# 03_ANALOG.net
KiCad netlist of a schematic drawn in Altium Designer
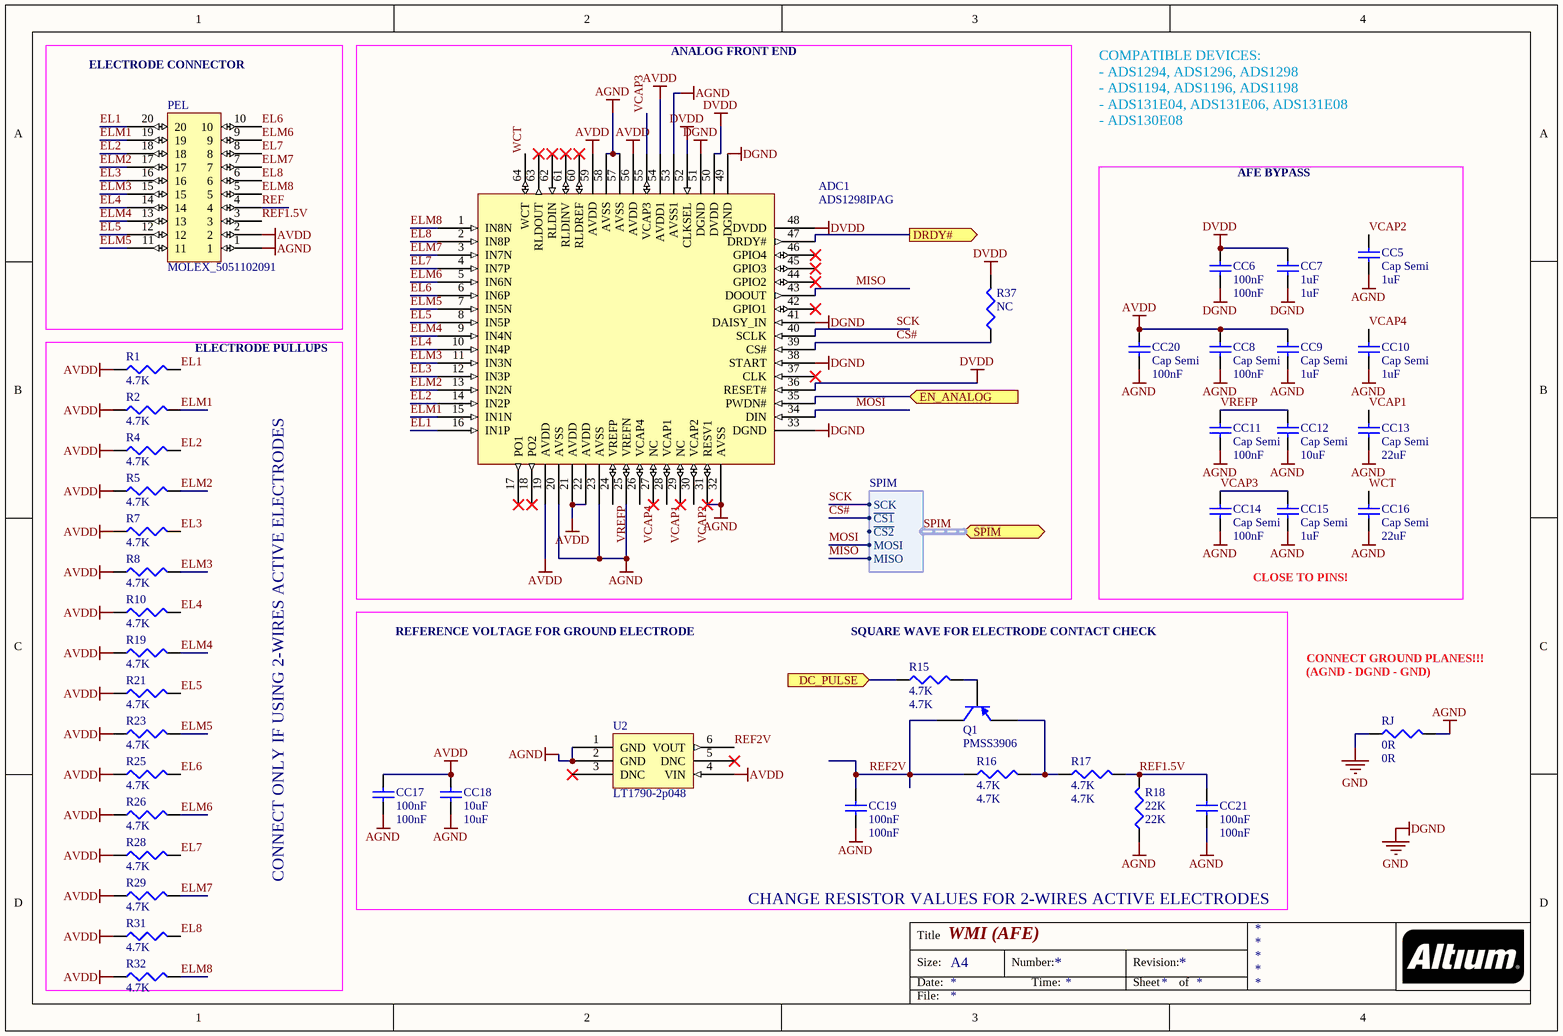
[diagram p0: 03_ANALOG.SchDoc]

(export (version "E")
  (design (tool "Eeschema 10.0.6"))
  (components
    (comp (ref "ADC1")
      (value "ADS1298IPAG")
      (footprint "Atmel Microcontroller 32-Bit ARM:LQFP64_M")
      (libsource (lib "Schlib1") (part "ADS1298"))
    )
    (comp (ref "CC5")
      (value "Cap Semi")
      (footprint "0402")
      (description "Capacitor (Semiconductor SIM Model)")
      (fields (field (name "ALTIUM_VALUE") "1uF") (field (name "PUBLISHER") "Altium Limited"))
      (libsource (lib "Miscellaneous Devices") (part "Cap Semi"))
    )
    (comp (ref "CC6")
      (value "100nF")
      (footprint "0402")
      (description "Capacitor (Semiconductor SIM Model)")
      (fields (field (name "ALTIUM_VALUE") "100nF") (field (name "PUBLISHER") "Altium Limited"))
      (libsource (lib "Miscellaneous Devices") (part "Cap Semi"))
    )
    (comp (ref "CC7")
      (value "1uF")
      (footprint "0402")
      (description "Capacitor (Semiconductor SIM Model)")
      (fields (field (name "ALTIUM_VALUE") "1uF") (field (name "PUBLISHER") "Altium Limited"))
      (libsource (lib "Miscellaneous Devices") (part "Cap Semi"))
    )
    (comp (ref "CC8")
      (value "Cap Semi")
      (footprint "0402")
      (description "Capacitor (Semiconductor SIM Model)")
      (fields (field (name "ALTIUM_VALUE") "100nF") (field (name "PUBLISHER") "Altium Limited"))
      (libsource (lib "Miscellaneous Devices") (part "Cap Semi"))
    )
    (comp (ref "CC9")
      (value "Cap Semi")
      (footprint "0402")
      (description "Capacitor (Semiconductor SIM Model)")
      (fields (field (name "ALTIUM_VALUE") "1uF") (field (name "PUBLISHER") "Altium Limited"))
      (libsource (lib "Miscellaneous Devices") (part "Cap Semi"))
    )
    (comp (ref "CC10")
      (value "Cap Semi")
      (footprint "0402")
      (description "Capacitor (Semiconductor SIM Model)")
      (fields (field (name "ALTIUM_VALUE") "1uF") (field (name "PUBLISHER") "Altium Limited"))
      (libsource (lib "Miscellaneous Devices") (part "Cap Semi"))
    )
    (comp (ref "CC11")
      (value "Cap Semi")
      (footprint "0402")
      (description "Capacitor (Semiconductor SIM Model)")
      (fields (field (name "ALTIUM_VALUE") "100nF") (field (name "PUBLISHER") "Altium Limited"))
      (libsource (lib "Miscellaneous Devices") (part "Cap Semi"))
    )
    (comp (ref "CC12")
      (value "Cap Semi")
      (footprint "0402")
      (description "Capacitor (Semiconductor SIM Model)")
      (fields (field (name "ALTIUM_VALUE") "10uF") (field (name "PUBLISHER") "Altium Limited"))
      (libsource (lib "Miscellaneous Devices") (part "Cap Semi"))
    )
    (comp (ref "CC13")
      (value "Cap Semi")
      (footprint "J1-0603")
      (description "Capacitor (Semiconductor SIM Model)")
      (fields (field (name "ALTIUM_VALUE") "22uF") (field (name "PUBLISHER") "Altium Limited"))
      (libsource (lib "Miscellaneous Devices") (part "Cap Semi"))
    )
    (comp (ref "CC14")
      (value "Cap Semi")
      (footprint "0402")
      (description "Capacitor (Semiconductor SIM Model)")
      (fields (field (name "ALTIUM_VALUE") "100nF") (field (name "PUBLISHER") "Altium Limited"))
      (libsource (lib "Miscellaneous Devices") (part "Cap Semi"))
    )
    (comp (ref "CC15")
      (value "Cap Semi")
      (footprint "0402")
      (description "Capacitor (Semiconductor SIM Model)")
      (fields (field (name "ALTIUM_VALUE") "1uF") (field (name "PUBLISHER") "Altium Limited"))
      (libsource (lib "Miscellaneous Devices") (part "Cap Semi"))
    )
    (comp (ref "CC16")
      (value "Cap Semi")
      (footprint "1608[0603]")
      (description "Capacitor (Semiconductor SIM Model)")
      (fields (field (name "ALTIUM_VALUE") "22uF") (field (name "PUBLISHER") "Altium Limited"))
      (libsource (lib "Miscellaneous Devices") (part "Cap Semi"))
    )
    (comp (ref "CC17")
      (value "100nF")
      (footprint "0402")
      (description "Capacitor (Semiconductor SIM Model)")
      (fields (field (name "ALTIUM_VALUE") "100nF") (field (name "PUBLISHER") "Altium Limited"))
      (libsource (lib "Miscellaneous Devices") (part "Cap Semi"))
    )
    (comp (ref "CC18")
      (value "10uF")
      (footprint "0402")
      (description "Capacitor (Semiconductor SIM Model)")
      (fields (field (name "ALTIUM_VALUE") "10uF") (field (name "PUBLISHER") "Altium Limited"))
      (libsource (lib "Miscellaneous Devices") (part "Cap Semi"))
    )
    (comp (ref "CC19")
      (value "100nF")
      (footprint "0402")
      (description "Capacitor (Semiconductor SIM Model)")
      (fields (field (name "ALTIUM_VALUE") "100nF") (field (name "PUBLISHER") "Altium Limited"))
      (libsource (lib "Miscellaneous Devices") (part "Cap Semi"))
    )
    (comp (ref "CC20")
      (value "Cap Semi")
      (footprint "0402")
      (description "Capacitor (Semiconductor SIM Model)")
      (fields (field (name "ALTIUM_VALUE") "100nF") (field (name "PUBLISHER") "Altium Limited"))
      (libsource (lib "Miscellaneous Devices") (part "Cap Semi"))
    )
    (comp (ref "CC21")
      (value "100nF")
      (footprint "0402")
      (description "Capacitor (Semiconductor SIM Model)")
      (fields (field (name "ALTIUM_VALUE") "100nF") (field (name "PUBLISHER") "Altium Limited"))
      (libsource (lib "Miscellaneous Devices") (part "Cap Semi"))
    )
    (comp (ref "PEL")
      (value "MOLEX_5051102091")
      (footprint "MOLEX_5051102091")
      (libsource (lib "Schlib1") (part "MOLEX_5051102091"))
    )
    (comp (ref "Q1")
      (value "PMSS3906")
      (footprint "SOT323_N")
      (description "PNP Switching Transistor")
      (fields (field (name "PUBLISHER") "Altium Limited"))
      (libsource (lib "Philips Discrete BJT - Low Power") (part "PMSS3906"))
    )
    (comp (ref "R1")
      (value "4.7K")
      (footprint "0402")
      (description "Resistor")
      (fields (field (name "PUBLISHER") "Altium Limited"))
      (libsource (lib "Miscellaneous Devices") (part "Res3"))
    )
    (comp (ref "R2")
      (value "4.7K")
      (footprint "0402")
      (description "Resistor")
      (fields (field (name "PUBLISHER") "Altium Limited"))
      (libsource (lib "Miscellaneous Devices") (part "Res3"))
    )
    (comp (ref "R4")
      (value "4.7K")
      (footprint "0402")
      (description "Resistor")
      (fields (field (name "PUBLISHER") "Altium Limited"))
      (libsource (lib "Miscellaneous Devices") (part "Res3"))
    )
    (comp (ref "R5")
      (value "4.7K")
      (footprint "0402")
      (description "Resistor")
      (fields (field (name "PUBLISHER") "Altium Limited"))
      (libsource (lib "Miscellaneous Devices") (part "Res3"))
    )
    (comp (ref "R7")
      (value "4.7K")
      (footprint "0402")
      (description "Resistor")
      (fields (field (name "PUBLISHER") "Altium Limited"))
      (libsource (lib "Miscellaneous Devices") (part "Res3"))
    )
    (comp (ref "R8")
      (value "4.7K")
      (footprint "0402")
      (description "Resistor")
      (fields (field (name "PUBLISHER") "Altium Limited"))
      (libsource (lib "Miscellaneous Devices") (part "Res3"))
    )
    (comp (ref "R10")
      (value "4.7K")
      (footprint "0402")
      (description "Resistor")
      (fields (field (name "PUBLISHER") "Altium Limited"))
      (libsource (lib "Miscellaneous Devices") (part "Res3"))
    )
    (comp (ref "R15")
      (value "4.7K")
      (footprint "0402")
      (description "Resistor")
      (fields (field (name "ALTIUM_VALUE") "4.7K") (field (name "PUBLISHER") "Altium Limited"))
      (libsource (lib "Miscellaneous Devices") (part "Res3"))
    )
    (comp (ref "R16")
      (value "4.7K")
      (footprint "0402")
      (description "Resistor")
      (fields (field (name "ALTIUM_VALUE") "4.7K") (field (name "PUBLISHER") "Altium Limited"))
      (libsource (lib "Miscellaneous Devices") (part "Res3"))
    )
    (comp (ref "R17")
      (value "4.7K")
      (footprint "0402")
      (description "Resistor")
      (fields (field (name "ALTIUM_VALUE") "4.7K") (field (name "PUBLISHER") "Altium Limited"))
      (libsource (lib "Miscellaneous Devices") (part "Res3"))
    )
    (comp (ref "R18")
      (value "22K")
      (footprint "0402")
      (description "Resistor")
      (fields (field (name "ALTIUM_VALUE") "22K") (field (name "PUBLISHER") "Altium Limited"))
      (libsource (lib "Miscellaneous Devices") (part "Res3"))
    )
    (comp (ref "R19")
      (value "4.7K")
      (footprint "0402")
      (description "Resistor")
      (fields (field (name "PUBLISHER") "Altium Limited"))
      (libsource (lib "Miscellaneous Devices") (part "Res3"))
    )
    (comp (ref "R21")
      (value "4.7K")
      (footprint "0402")
      (description "Resistor")
      (fields (field (name "PUBLISHER") "Altium Limited"))
      (libsource (lib "Miscellaneous Devices") (part "Res3"))
    )
    (comp (ref "R23")
      (value "4.7K")
      (footprint "0402")
      (description "Resistor")
      (fields (field (name "PUBLISHER") "Altium Limited"))
      (libsource (lib "Miscellaneous Devices") (part "Res3"))
    )
    (comp (ref "R25")
      (value "4.7K")
      (footprint "0402")
      (description "Resistor")
      (fields (field (name "PUBLISHER") "Altium Limited"))
      (libsource (lib "Miscellaneous Devices") (part "Res3"))
    )
    (comp (ref "R26")
      (value "4.7K")
      (footprint "0402")
      (description "Resistor")
      (fields (field (name "PUBLISHER") "Altium Limited"))
      (libsource (lib "Miscellaneous Devices") (part "Res3"))
    )
    (comp (ref "R28")
      (value "4.7K")
      (footprint "0402")
      (description "Resistor")
      (fields (field (name "PUBLISHER") "Altium Limited"))
      (libsource (lib "Miscellaneous Devices") (part "Res3"))
    )
    (comp (ref "R29")
      (value "4.7K")
      (footprint "0402")
      (description "Resistor")
      (fields (field (name "PUBLISHER") "Altium Limited"))
      (libsource (lib "Miscellaneous Devices") (part "Res3"))
    )
    (comp (ref "R31")
      (value "4.7K")
      (footprint "0402")
      (description "Resistor")
      (fields (field (name "PUBLISHER") "Altium Limited"))
      (libsource (lib "Miscellaneous Devices") (part "Res3"))
    )
    (comp (ref "R32")
      (value "4.7K")
      (footprint "0402")
      (description "Resistor")
      (fields (field (name "PUBLISHER") "Altium Limited"))
      (libsource (lib "Miscellaneous Devices") (part "Res3"))
    )
    (comp (ref "R37")
      (value "NC")
      (footprint "0402")
      (description "Resistor")
      (fields (field (name "PUBLISHER") "Altium Limited"))
      (libsource (lib "Miscellaneous Devices") (part "Res3"))
    )
    (comp (ref "RJ")
      (value "0R")
      (footprint "0402")
      (description "Resistor")
      (fields (field (name "ALTIUM_VALUE") "0R") (field (name "PUBLISHER") "Altium Limited"))
      (libsource (lib "Miscellaneous Devices") (part "Res3"))
    )
    (comp (ref "U2")
      (value "LT1790-2p048")
      (footprint "SOT-23_A_N")
      (libsource (lib "Schlib1") (part "LT1790"))
    )
  )
  (nets
    (net (code "2") (name "/CS#") (class "Default")
      (node (ref "ADC1") (pin "39") (pinfunction "CS#_39") (pintype "input"))
      (node (ref "R37") (pin "1") (pinfunction "1_1") (pintype "passive"))
    )
    (net (code "3") (name "/DC_PULSE") (class "Default")
      (node (ref "R15") (pin "1") (pinfunction "1_1") (pintype "passive"))
    )
    (net (code "4") (name "/DRDY#") (class "Default")
      (node (ref "ADC1") (pin "47") (pinfunction "DRDY#_47") (pintype "output"))
    )
    (net (code "5") (name "/EL1") (class "Default")
      (node (ref "ADC1") (pin "16") (pinfunction "IN1P_16") (pintype "input"))
      (node (ref "PEL") (pin "20") (pinfunction "20_20") (pintype "bidirectional"))
      (node (ref "R1") (pin "2") (pinfunction "2_2") (pintype "passive"))
    )
    (net (code "6") (name "/EL2") (class "Default")
      (node (ref "ADC1") (pin "14") (pinfunction "IN2P_14") (pintype "input"))
      (node (ref "PEL") (pin "18") (pinfunction "18_18") (pintype "bidirectional"))
      (node (ref "R4") (pin "2") (pinfunction "2_2") (pintype "passive"))
    )
    (net (code "7") (name "/EL3") (class "Default")
      (node (ref "ADC1") (pin "12") (pinfunction "IN3P_12") (pintype "input"))
      (node (ref "PEL") (pin "16") (pinfunction "16_16") (pintype "bidirectional"))
      (node (ref "R7") (pin "2") (pinfunction "2_2") (pintype "passive"))
    )
    (net (code "8") (name "/EL4") (class "Default")
      (node (ref "ADC1") (pin "10") (pinfunction "IN4P_10") (pintype "input"))
      (node (ref "PEL") (pin "14") (pinfunction "14_14") (pintype "bidirectional"))
      (node (ref "R10") (pin "2") (pinfunction "2_2") (pintype "passive"))
    )
    (net (code "9") (name "/EL5") (class "Default")
      (node (ref "ADC1") (pin "8") (pinfunction "IN5P_8") (pintype "input"))
      (node (ref "PEL") (pin "12") (pinfunction "12_12") (pintype "bidirectional"))
      (node (ref "R21") (pin "2") (pinfunction "2_2") (pintype "passive"))
    )
    (net (code "10") (name "/EL6") (class "Default")
      (node (ref "ADC1") (pin "6") (pinfunction "IN6P_6") (pintype "input"))
      (node (ref "PEL") (pin "10") (pinfunction "10_10") (pintype "bidirectional"))
      (node (ref "R25") (pin "2") (pinfunction "2_2") (pintype "passive"))
    )
    (net (code "11") (name "/EL7") (class "Default")
      (node (ref "ADC1") (pin "4") (pinfunction "IN7P_4") (pintype "input"))
      (node (ref "PEL") (pin "8") (pinfunction "8_8") (pintype "bidirectional"))
      (node (ref "R28") (pin "2") (pinfunction "2_2") (pintype "passive"))
    )
    (net (code "12") (name "/EL8") (class "Default")
      (node (ref "ADC1") (pin "2") (pinfunction "IN8P_2") (pintype "input"))
      (node (ref "PEL") (pin "6") (pinfunction "6_6") (pintype "bidirectional"))
      (node (ref "R31") (pin "2") (pinfunction "2_2") (pintype "passive"))
    )
    (net (code "13") (name "/ELM1") (class "Default")
      (node (ref "ADC1") (pin "15") (pinfunction "IN1N_15") (pintype "input"))
      (node (ref "PEL") (pin "19") (pinfunction "19_19") (pintype "bidirectional"))
      (node (ref "R2") (pin "2") (pinfunction "2_2") (pintype "passive"))
    )
    (net (code "14") (name "/ELM2") (class "Default")
      (node (ref "ADC1") (pin "13") (pinfunction "IN2N_13") (pintype "input"))
      (node (ref "PEL") (pin "17") (pinfunction "17_17") (pintype "bidirectional"))
      (node (ref "R5") (pin "2") (pinfunction "2_2") (pintype "passive"))
    )
    (net (code "15") (name "/ELM3") (class "Default")
      (node (ref "ADC1") (pin "11") (pinfunction "IN3N_11") (pintype "input"))
      (node (ref "PEL") (pin "15") (pinfunction "15_15") (pintype "bidirectional"))
      (node (ref "R8") (pin "2") (pinfunction "2_2") (pintype "passive"))
    )
    (net (code "16") (name "/ELM4") (class "Default")
      (node (ref "ADC1") (pin "9") (pinfunction "IN4N_9") (pintype "input"))
      (node (ref "PEL") (pin "13") (pinfunction "13_13") (pintype "bidirectional"))
      (node (ref "R19") (pin "2") (pinfunction "2_2") (pintype "passive"))
    )
    (net (code "17") (name "/ELM5") (class "Default")
      (node (ref "ADC1") (pin "7") (pinfunction "IN5N_7") (pintype "input"))
      (node (ref "PEL") (pin "11") (pinfunction "11_11") (pintype "bidirectional"))
      (node (ref "R23") (pin "2") (pinfunction "2_2") (pintype "passive"))
    )
    (net (code "18") (name "/ELM6") (class "Default")
      (node (ref "ADC1") (pin "5") (pinfunction "IN6N_5") (pintype "input"))
      (node (ref "PEL") (pin "9") (pinfunction "9_9") (pintype "bidirectional"))
      (node (ref "R26") (pin "2") (pinfunction "2_2") (pintype "passive"))
    )
    (net (code "19") (name "/ELM7") (class "Default")
      (node (ref "ADC1") (pin "3") (pinfunction "IN7N_3") (pintype "input"))
      (node (ref "PEL") (pin "7") (pinfunction "7_7") (pintype "bidirectional"))
      (node (ref "R29") (pin "2") (pinfunction "2_2") (pintype "passive"))
    )
    (net (code "20") (name "/ELM8") (class "Default")
      (node (ref "ADC1") (pin "1") (pinfunction "IN8N_1") (pintype "input"))
      (node (ref "PEL") (pin "5") (pinfunction "5_5") (pintype "bidirectional"))
      (node (ref "R32") (pin "2") (pinfunction "2_2") (pintype "passive"))
    )
    (net (code "21") (name "/EN_ANALOG") (class "Default")
      (node (ref "ADC1") (pin "35") (pinfunction "PWDN#_35") (pintype "input"))
    )
    (net (code "22") (name "/MISO") (class "Default")
      (node (ref "ADC1") (pin "43") (pinfunction "DOOUT_43") (pintype "output"))
    )
    (net (code "23") (name "/MOSI") (class "Default")
      (node (ref "ADC1") (pin "34") (pinfunction "DIN_34") (pintype "input"))
    )
    (net (code "24") (name "/REF") (class "Default")
      (node (ref "PEL") (pin "4") (pinfunction "4_4") (pintype "bidirectional"))
    )
    (net (code "25") (name "/REF1.5V") (class "Default")
      (node (ref "CC21") (pin "2") (pinfunction "2_2") (pintype "passive"))
      (node (ref "PEL") (pin "3") (pinfunction "3_3") (pintype "bidirectional"))
      (node (ref "R17") (pin "2") (pinfunction "2_2") (pintype "passive"))
      (node (ref "R18") (pin "2") (pinfunction "2_2") (pintype "passive"))
    )
    (net (code "26") (name "/REF2V") (class "Default")
      (node (ref "CC19") (pin "2") (pinfunction "2_2") (pintype "passive"))
      (node (ref "Q1") (pin "3") (pinfunction "C_3") (pintype "passive"))
      (node (ref "R16") (pin "1") (pinfunction "1_1") (pintype "passive"))
      (node (ref "U2") (pin "6") (pinfunction "VOUT_6") (pintype "output"))
    )
    (net (code "27") (name "/SCK") (class "Default")
      (node (ref "ADC1") (pin "40") (pinfunction "SCLK_40") (pintype "input"))
    )
    (net (code "29") (name "/VCAP1") (class "Default")
      (node (ref "ADC1") (pin "28") (pinfunction "VCAP1_28") (pintype "bidirectional"))
      (node (ref "CC13") (pin "2") (pinfunction "2_2") (pintype "passive"))
    )
    (net (code "30") (name "/VCAP2") (class "Default")
      (node (ref "ADC1") (pin "30") (pinfunction "VCAP2_30") (pintype "bidirectional"))
      (node (ref "CC5") (pin "2") (pinfunction "2_2") (pintype "passive"))
    )
    (net (code "31") (name "/VCAP3") (class "Default")
      (node (ref "ADC1") (pin "55") (pinfunction "VCAP3_55") (pintype "bidirectional"))
      (node (ref "CC14") (pin "2") (pinfunction "2_2") (pintype "passive"))
      (node (ref "CC15") (pin "2") (pinfunction "2_2") (pintype "passive"))
    )
    (net (code "32") (name "/VCAP4") (class "Default")
      (node (ref "ADC1") (pin "26") (pinfunction "VCAP4_26") (pintype "bidirectional"))
      (node (ref "CC10") (pin "2") (pinfunction "2_2") (pintype "passive"))
    )
    (net (code "33") (name "/VREFP") (class "Default")
      (node (ref "ADC1") (pin "24") (pinfunction "VREFP_24") (pintype "bidirectional"))
      (node (ref "CC11") (pin "2") (pinfunction "2_2") (pintype "passive"))
      (node (ref "CC12") (pin "2") (pinfunction "2_2") (pintype "passive"))
    )
    (net (code "34") (name "/WCT") (class "Default")
      (node (ref "ADC1") (pin "64") (pinfunction "WCT_64") (pintype "bidirectional"))
      (node (ref "CC16") (pin "2") (pinfunction "2_2") (pintype "passive"))
    )
    (net (code "35") (name "AGND") (class "Default")
      (node (ref "ADC1") (pin "20") (pinfunction "AVSS_20") (pintype "power_in"))
      (node (ref "ADC1") (pin "23") (pinfunction "AVSS_23") (pintype "power_in"))
      (node (ref "ADC1") (pin "25") (pinfunction "VREFN_25") (pintype "bidirectional"))
      (node (ref "ADC1") (pin "31") (pinfunction "RESV1_31") (pintype "bidirectional"))
      (node (ref "ADC1") (pin "32") (pinfunction "AVSS_32") (pintype "power_in"))
      (node (ref "ADC1") (pin "53") (pinfunction "AVSS1_53") (pintype "power_in"))
      (node (ref "ADC1") (pin "57") (pinfunction "AVSS_57") (pintype "power_in"))
      (node (ref "ADC1") (pin "58") (pinfunction "AVSS_58") (pintype "power_in"))
      (node (ref "CC10") (pin "1") (pinfunction "1_1") (pintype "passive"))
      (node (ref "CC11") (pin "1") (pinfunction "1_1") (pintype "passive"))
      (node (ref "CC12") (pin "1") (pinfunction "1_1") (pintype "passive"))
      (node (ref "CC13") (pin "1") (pinfunction "1_1") (pintype "passive"))
      (node (ref "CC14") (pin "1") (pinfunction "1_1") (pintype "passive"))
      (node (ref "CC15") (pin "1") (pinfunction "1_1") (pintype "passive"))
      (node (ref "CC16") (pin "1") (pinfunction "1_1") (pintype "passive"))
      (node (ref "CC17") (pin "1") (pinfunction "1_1") (pintype "passive"))
      (node (ref "CC18") (pin "1") (pinfunction "1_1") (pintype "passive"))
      (node (ref "CC19") (pin "1") (pinfunction "1_1") (pintype "passive"))
      (node (ref "CC20") (pin "1") (pinfunction "1_1") (pintype "passive"))
      (node (ref "CC21") (pin "1") (pinfunction "1_1") (pintype "passive"))
      (node (ref "CC5") (pin "1") (pinfunction "1_1") (pintype "passive"))
      (node (ref "CC8") (pin "1") (pinfunction "1_1") (pintype "passive"))
      (node (ref "CC9") (pin "1") (pinfunction "1_1") (pintype "passive"))
      (node (ref "PEL") (pin "1") (pinfunction "1_1") (pintype "bidirectional"))
      (node (ref "R18") (pin "1") (pinfunction "1_1") (pintype "passive"))
      (node (ref "RJ") (pin "2") (pinfunction "2_2") (pintype "passive"))
      (node (ref "U2") (pin "1") (pinfunction "GND_1") (pintype "power_in"))
      (node (ref "U2") (pin "2") (pinfunction "GND_2") (pintype "power_in"))
    )
    (net (code "36") (name "AVDD") (class "Default")
      (node (ref "ADC1") (pin "19") (pinfunction "AVDD_19") (pintype "power_in"))
      (node (ref "ADC1") (pin "21") (pinfunction "AVDD_21") (pintype "power_in"))
      (node (ref "ADC1") (pin "22") (pinfunction "AVDD_22") (pintype "power_in"))
      (node (ref "ADC1") (pin "54") (pinfunction "AVDD1_54") (pintype "power_in"))
      (node (ref "ADC1") (pin "56") (pinfunction "AVDD_56") (pintype "power_in"))
      (node (ref "ADC1") (pin "59") (pinfunction "AVDD_59") (pintype "power_in"))
      (node (ref "CC17") (pin "2") (pinfunction "2_2") (pintype "passive"))
      (node (ref "CC18") (pin "2") (pinfunction "2_2") (pintype "passive"))
      (node (ref "CC20") (pin "2") (pinfunction "2_2") (pintype "passive"))
      (node (ref "CC8") (pin "2") (pinfunction "2_2") (pintype "passive"))
      (node (ref "CC9") (pin "2") (pinfunction "2_2") (pintype "passive"))
      (node (ref "PEL") (pin "2") (pinfunction "2_2") (pintype "bidirectional"))
      (node (ref "R1") (pin "1") (pinfunction "1_1") (pintype "passive"))
      (node (ref "R10") (pin "1") (pinfunction "1_1") (pintype "passive"))
      (node (ref "R19") (pin "1") (pinfunction "1_1") (pintype "passive"))
      (node (ref "R2") (pin "1") (pinfunction "1_1") (pintype "passive"))
      (node (ref "R21") (pin "1") (pinfunction "1_1") (pintype "passive"))
      (node (ref "R23") (pin "1") (pinfunction "1_1") (pintype "passive"))
      (node (ref "R25") (pin "1") (pinfunction "1_1") (pintype "passive"))
      (node (ref "R26") (pin "1") (pinfunction "1_1") (pintype "passive"))
      (node (ref "R28") (pin "1") (pinfunction "1_1") (pintype "passive"))
      (node (ref "R29") (pin "1") (pinfunction "1_1") (pintype "passive"))
      (node (ref "R31") (pin "1") (pinfunction "1_1") (pintype "passive"))
      (node (ref "R32") (pin "1") (pinfunction "1_1") (pintype "passive"))
      (node (ref "R4") (pin "1") (pinfunction "1_1") (pintype "passive"))
      (node (ref "R5") (pin "1") (pinfunction "1_1") (pintype "passive"))
      (node (ref "R7") (pin "1") (pinfunction "1_1") (pintype "passive"))
      (node (ref "R8") (pin "1") (pinfunction "1_1") (pintype "passive"))
      (node (ref "U2") (pin "4") (pinfunction "VIN_4") (pintype "input"))
    )
    (net (code "37") (name "DGND") (class "Default")
      (node (ref "ADC1") (pin "33") (pinfunction "DGND_33") (pintype "power_in"))
      (node (ref "ADC1") (pin "38") (pinfunction "START_38") (pintype "input"))
      (node (ref "ADC1") (pin "41") (pinfunction "DAISY_IN_41") (pintype "input"))
      (node (ref "ADC1") (pin "49") (pinfunction "DGND_49") (pintype "power_in"))
      (node (ref "ADC1") (pin "51") (pinfunction "DGND_51") (pintype "power_in"))
      (node (ref "CC6") (pin "1") (pinfunction "1_1") (pintype "passive"))
      (node (ref "CC7") (pin "1") (pinfunction "1_1") (pintype "passive"))
      (node (ref "RJ") (pin "1") (pinfunction "1_1") (pintype "passive"))
    )
    (net (code "38") (name "DVDD") (class "Default")
      (node (ref "ADC1") (pin "36") (pinfunction "RESET#_36") (pintype "input"))
      (node (ref "ADC1") (pin "48") (pinfunction "DVDD_48") (pintype "power_in"))
      (node (ref "ADC1") (pin "50") (pinfunction "DVDD_50") (pintype "power_in"))
      (node (ref "ADC1") (pin "52") (pinfunction "CLKSEL_52") (pintype "input"))
      (node (ref "CC6") (pin "2") (pinfunction "2_2") (pintype "passive"))
      (node (ref "CC7") (pin "2") (pinfunction "2_2") (pintype "passive"))
      (node (ref "R37") (pin "2") (pinfunction "2_2") (pintype "passive"))
    )
    (net (code "39") (name "Net-(Q1-B)") (class "Default")
      (node (ref "Q1") (pin "1") (pinfunction "B_1") (pintype "passive"))
      (node (ref "R15") (pin "2") (pinfunction "2_2") (pintype "passive"))
    )
    (net (code "40") (name "Net-(Q1-E)") (class "Default")
      (node (ref "Q1") (pin "2") (pinfunction "E_2") (pintype "passive"))
      (node (ref "R16") (pin "2") (pinfunction "2_2") (pintype "passive"))
      (node (ref "R17") (pin "1") (pinfunction "1_1") (pintype "passive"))
    )
    (net (code "41") (name "unconnected-(ADC1-CLK-Pad37)") (class "Default")
      (node (ref "ADC1") (pin "37") (pinfunction "CLK_37") (pintype "input+no_connect"))
    )
    (net (code "42") (name "unconnected-(ADC1-GPIO1-Pad42)") (class "Default")
      (node (ref "ADC1") (pin "42") (pinfunction "GPIO1_42") (pintype "bidirectional+no_connect"))
    )
    (net (code "43") (name "unconnected-(ADC1-GPIO2-Pad44)") (class "Default")
      (node (ref "ADC1") (pin "44") (pinfunction "GPIO2_44") (pintype "bidirectional+no_connect"))
    )
    (net (code "44") (name "unconnected-(ADC1-GPIO3-Pad45)") (class "Default")
      (node (ref "ADC1") (pin "45") (pinfunction "GPIO3_45") (pintype "bidirectional+no_connect"))
    )
    (net (code "45") (name "unconnected-(ADC1-GPIO4-Pad46)") (class "Default")
      (node (ref "ADC1") (pin "46") (pinfunction "GPIO4_46") (pintype "bidirectional+no_connect"))
    )
    (net (code "46") (name "unconnected-(ADC1-NC-Pad27)") (class "Default")
      (node (ref "ADC1") (pin "27") (pinfunction "NC_27") (pintype "bidirectional+no_connect"))
    )
    (net (code "47") (name "unconnected-(ADC1-NC-Pad29)") (class "Default")
      (node (ref "ADC1") (pin "29") (pinfunction "NC_29") (pintype "bidirectional+no_connect"))
    )
    (net (code "48") (name "unconnected-(ADC1-PO1-Pad17)") (class "Default")
      (node (ref "ADC1") (pin "17") (pinfunction "PO1_17") (pintype "output+no_connect"))
    )
    (net (code "49") (name "unconnected-(ADC1-PO2-Pad18)") (class "Default")
      (node (ref "ADC1") (pin "18") (pinfunction "PO2_18") (pintype "output+no_connect"))
    )
    (net (code "50") (name "unconnected-(ADC1-RLDIN-Pad62)") (class "Default")
      (node (ref "ADC1") (pin "62") (pinfunction "RLDIN_62") (pintype "input+no_connect"))
    )
    (net (code "51") (name "unconnected-(ADC1-RLDINV-Pad61)") (class "Default")
      (node (ref "ADC1") (pin "61") (pinfunction "RLDINV_61") (pintype "bidirectional+no_connect"))
    )
    (net (code "52") (name "unconnected-(ADC1-RLDOUT-Pad63)") (class "Default")
      (node (ref "ADC1") (pin "63") (pinfunction "RLDOUT_63") (pintype "output+no_connect"))
    )
    (net (code "53") (name "unconnected-(ADC1-RLDREF-Pad60)") (class "Default")
      (node (ref "ADC1") (pin "60") (pinfunction "RLDREF_60") (pintype "bidirectional+no_connect"))
    )
    (net (code "54") (name "unconnected-(U2-DNC-Pad3)") (class "Default")
      (node (ref "U2") (pin "3") (pinfunction "DNC_3") (pintype "passive+no_connect"))
    )
    (net (code "55") (name "unconnected-(U2-DNC-Pad5)") (class "Default")
      (node (ref "U2") (pin "5") (pinfunction "DNC_5") (pintype "passive+no_connect"))
    )
  )
)
